# 2_SoC_schdoc.net
KiCad netlist of a schematic drawn in Altium Designer
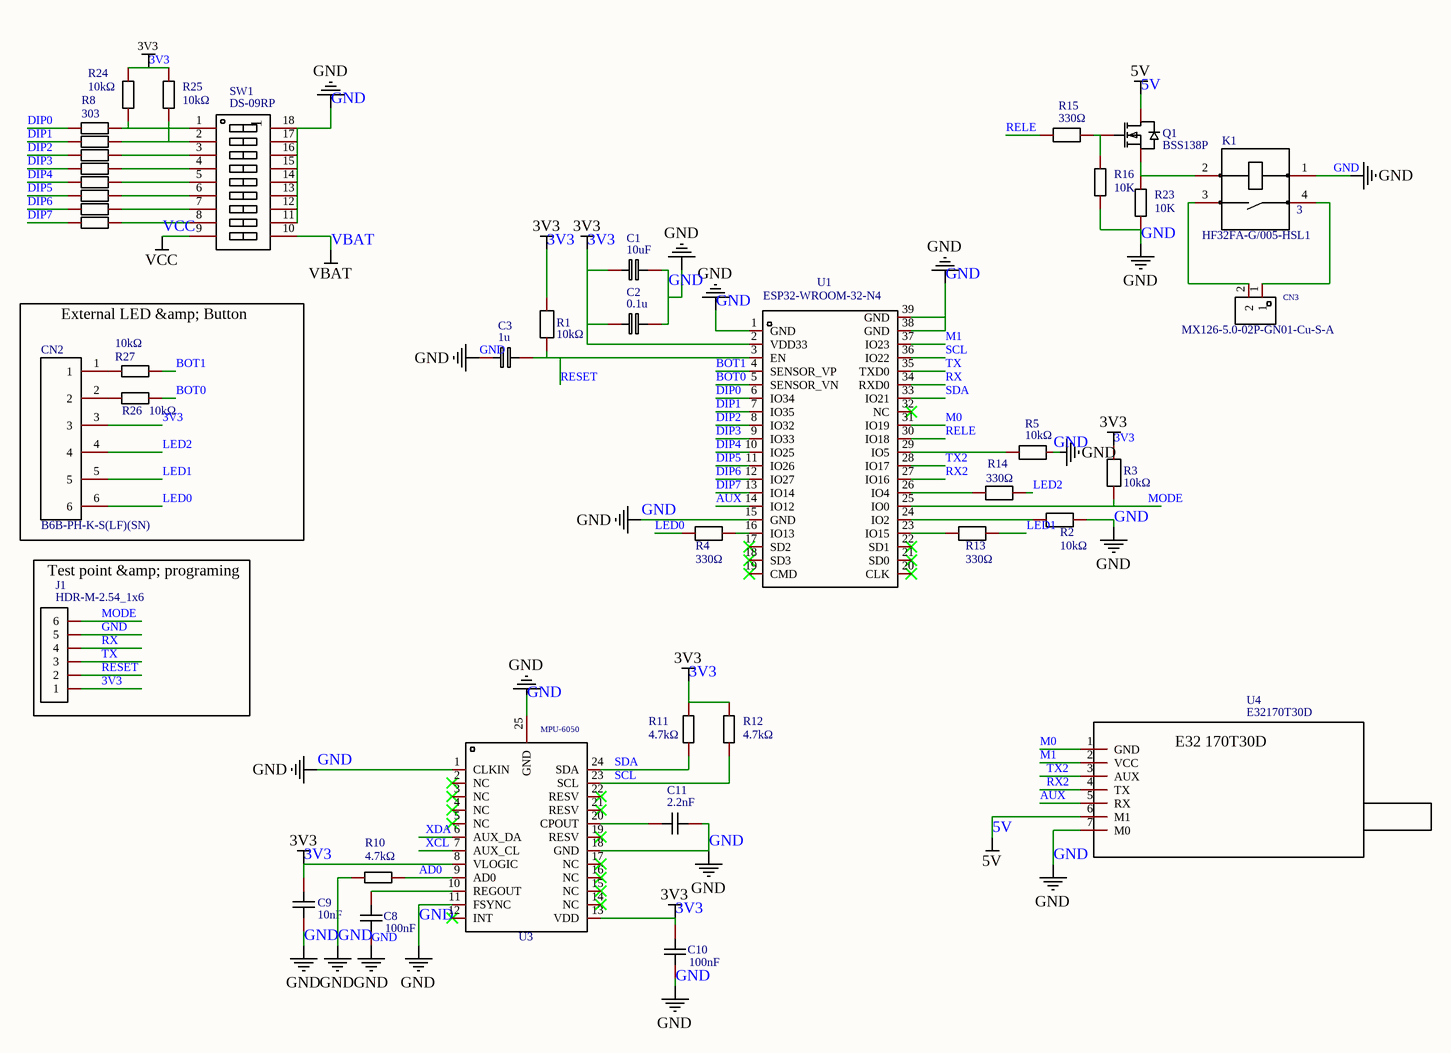
[diagram p0: 2_SoC.schdoc.schdoc]

(export (version "E")
  (design (tool "Eeschema 10.0.6"))
  (components
    (comp (ref "C1")
      (value "10uF")
      (fields
        (field (name "NAME") "10uF")
        (field (name "MANUFACTURER") "SAMSUNG(三星)")
        (field (name "MANUFACTURER PART") "CL10A106MQ8NNNC")
        (field (name "TOLERANCE") "±20%")
      )
      (libsource (lib "altium-import") (part "root_0_CL10A106MQ8NNNC_"))
    )
    (comp (ref "C2")
      (value "0.1u")
      (fields
        (field (name "NAME") "0.1u")
        (field (name "MANUFACTURER PART") "C0603C104K5RACAUTO")
        (field (name "MANUFACTURER") "KEMET(基美)")
      )
      (libsource (lib "altium-import") (part "root_0_0.1u_"))
    )
    (comp (ref "C3")
      (value "1u")
      (fields
        (field (name "NAME") "1u")
        (field (name "MANUFACTURER PART") "CC0603ZRY5V8BB105")
        (field (name "MANUFACTURER") "YAGEO(国巨)")
      )
      (libsource (lib "altium-import") (part "root_0_1u_"))
    )
    (comp (ref "C8")
      (value "100nF")
      (fields
        (field (name "NAME") "100nF")
        (field (name "MANUFACTURER") "FOJAN(富捷)")
        (field (name "MANUFACTURER PART") "FCC0402B104K250AT")
        (field (name "TOLERANCE") "±10%")
      )
      (libsource (lib "altium-import") (part "root_0_FCC0402B104K250AT_"))
    )
    (comp (ref "C9")
      (value "10nF")
      (fields
        (field (name "NAME") "10nF")
        (field (name "MANUFACTURER") "YAGEO(国巨)")
        (field (name "MANUFACTURER PART") "CC0402KRX7R7BB103")
      )
      (libsource (lib "altium-import") (part "root_1_10nF_"))
    )
    (comp (ref "C10")
      (value "100nF")
      (fields
        (field (name "NAME") "100nF")
        (field (name "MANUFACTURER") "FOJAN(富捷)")
        (field (name "MANUFACTURER PART") "FCC0402B104K250AT")
        (field (name "TOLERANCE") "±10%")
      )
      (libsource (lib "altium-import") (part "root_0_FCC0402B104K250AT_"))
    )
    (comp (ref "C11")
      (value "2.2nF")
      (fields
        (field (name "NAME") "2.2nF")
        (field (name "MANUFACTURER") "YAGEO(国巨)")
        (field (name "MANUFACTURER PART") "CC0402KRX7R6BB222")
        (field (name "TOLERANCE") "±10%")
      )
      (libsource (lib "altium-import") (part "root_0_CC0402KRX7R6BB222_"))
    )
    (comp (ref "CN2")
      (value "B6B-PH-K-S(LF)(SN)")
      (fields (field (name "NAME") "B6B-PH-K-S(LF)(SN)") (field (name "MANUFACTURER") "JST"))
      (libsource (lib "altium-import") (part "root_0_B6B-PH-K-S(LF)(SN)_C131342_"))
    )
    (comp (ref "CN3")
      (value "MX126-5.0-02P-GN01-Cu-S-A")
      (fields (field (name "NAME") "MX126-5.0-02P-GN01-Cu-S-A") (field (name "MANUFACTURER") "MAX(迈旭)"))
      (libsource (lib "altium-import") (part "root_3_MX126-5.0-02P-GN01-Cu-S-A_"))
    )
    (comp (ref "J1")
      (value "HDR-M-2.54_1x6")
      (fields (field (name "NAME") "HDR-M-2.54_1x6"))
      (libsource (lib "altium-import") (part "root_2_HDR-M-2.54_1x6_"))
    )
    (comp (ref "K1")
      (value "HF32FA-G/005-HSL1")
      (fields
        (field (name "NAME") "HF32FA-G/005-HSL1")
        (field (name "MANUFACTURER") "HF(宏发)")
        (field (name "NUMBER") "3")
      )
      (libsource (lib "altium-import") (part "root_2_HF32FA-G/005-HSL1_"))
    )
    (comp (ref "Q1")
      (value "BSS138P")
      (fields (field (name "NAME") "BSS138P") (field (name "MANUFACTURER") "ElecSuper(静芯微）"))
      (libsource (lib "altium-import") (part "root_0_BSS138P_"))
    )
    (comp (ref "R1")
      (value "10kΩ")
      (description "Resistance: Tolerance:±1% Tolerance:±1%")
      (fields
        (field (name "NAME") "10kΩ")
        (field (name "MANUFACTURER") "VO(翔胜)")
        (field (name "MANUFACTURER PART") "SCR0402F10K")
      )
      (libsource (lib "altium-import") (part "root_1_SCR0402F10K_"))
    )
    (comp (ref "R2")
      (value "10kΩ")
      (description "Resistance: Tolerance:±1% Tolerance:±1%")
      (fields
        (field (name "NAME") "10kΩ")
        (field (name "MANUFACTURER") "VO(翔胜)")
        (field (name "MANUFACTURER PART") "SCR0402F10K")
      )
      (libsource (lib "altium-import") (part "root_0_SCR0402F10K_"))
    )
    (comp (ref "R3")
      (value "10kΩ")
      (description "Resistance: Tolerance:±1% Tolerance:±1%")
      (fields
        (field (name "NAME") "10kΩ")
        (field (name "MANUFACTURER") "VO(翔胜)")
        (field (name "MANUFACTURER PART") "SCR0402F10K")
      )
      (libsource (lib "altium-import") (part "root_1_SCR0402F10K_"))
    )
    (comp (ref "R4")
      (value "330Ω")
      (description "Resistance: Tolerance:±1% Tolerance:±1%")
      (fields
        (field (name "NAME") "330Ω")
        (field (name "MANUFACTURER") "VO(翔胜)")
        (field (name "MANUFACTURER PART") "SCR0603F330R")
      )
      (libsource (lib "altium-import") (part "root_0_SCR0603F330R_"))
    )
    (comp (ref "R5")
      (value "10kΩ")
      (description "Resistance: Tolerance:±1% Tolerance:±1%")
      (fields
        (field (name "NAME") "10kΩ")
        (field (name "MANUFACTURER") "VO(翔胜)")
        (field (name "MANUFACTURER PART") "SCR0402F10K")
      )
      (libsource (lib "altium-import") (part "root_0_SCR0402F10K_"))
    )
    (comp (ref "R8")
      (value "303")
      (fields (field (name "NAME") "303"))
      (libsource (lib "altium-import") (part "root_0_Res_0603_"))
    )
    (comp (ref "R9") (value "303") (libsource (lib "altium-import") (part "root_0_Res_0603_")))
    (comp (ref "R10")
      (value "4.7kΩ")
      (fields (field (name "NAME") "4.7kΩ"))
      (libsource (lib "altium-import") (part "root_2_Res_0603_"))
    )
    (comp (ref "R11")
      (value "4.7kΩ")
      (fields (field (name "NAME") "4.7kΩ"))
      (libsource (lib "altium-import") (part "root_1_Res_0603_"))
    )
    (comp (ref "R12")
      (value "4.7kΩ")
      (fields (field (name "NAME") "4.7kΩ"))
      (libsource (lib "altium-import") (part "root_1_Res_0603_"))
    )
    (comp (ref "R13")
      (value "330Ω")
      (description "Resistance: Tolerance:±1% Tolerance:±1%")
      (fields
        (field (name "NAME") "330Ω")
        (field (name "MANUFACTURER") "VO(翔胜)")
        (field (name "MANUFACTURER PART") "SCR0603F330R")
      )
      (libsource (lib "altium-import") (part "root_0_SCR0603F330R_"))
    )
    (comp (ref "R14")
      (value "330Ω")
      (description "Resistance: Tolerance:±1% Tolerance:±1%")
      (fields
        (field (name "NAME") "330Ω")
        (field (name "MANUFACTURER") "VO(翔胜)")
        (field (name "MANUFACTURER PART") "SCR0603F330R")
      )
      (libsource (lib "altium-import") (part "root_0_SCR0603F330R_"))
    )
    (comp (ref "R15")
      (value "330Ω")
      (description "Resistance: Tolerance:±1% Tolerance:±1%")
      (fields
        (field (name "NAME") "330Ω")
        (field (name "MANUFACTURER") "VO(翔胜)")
        (field (name "MANUFACTURER PART") "SCR0603F330R")
      )
      (libsource (lib "altium-import") (part "root_0_SCR0603F330R_"))
    )
    (comp (ref "R16")
      (value "10K")
      (fields (field (name "NAME") "10K"))
      (libsource (lib "altium-import") (part "root_1_Res_0603_"))
    )
    (comp (ref "R17") (value "303") (libsource (lib "altium-import") (part "root_0_Res_0603_")))
    (comp (ref "R18") (value "303") (libsource (lib "altium-import") (part "root_0_Res_0603_")))
    (comp (ref "R19") (value "303") (libsource (lib "altium-import") (part "root_0_Res_0603_")))
    (comp (ref "R20") (value "303") (libsource (lib "altium-import") (part "root_0_Res_0603_")))
    (comp (ref "R21") (value "303") (libsource (lib "altium-import") (part "root_0_Res_0603_")))
    (comp (ref "R22") (value "303") (libsource (lib "altium-import") (part "root_0_Res_0603_")))
    (comp (ref "R23")
      (value "10K")
      (fields (field (name "NAME") "10K"))
      (libsource (lib "altium-import") (part "root_1_Res_0603_"))
    )
    (comp (ref "R24")
      (value "10kΩ")
      (description "Resistance: Tolerance:±1% Tolerance:±1%")
      (fields
        (field (name "NAME") "10kΩ")
        (field (name "MANUFACTURER") "VO(翔胜)")
        (field (name "MANUFACTURER PART") "SCR0402F10K")
      )
      (libsource (lib "") (part "root_1_SCR0402F10K__1"))
    )
    (comp (ref "R25")
      (value "10kΩ")
      (description "Resistance: Tolerance:±1% Tolerance:±1%")
      (fields
        (field (name "NAME") "10kΩ")
        (field (name "MANUFACTURER") "VO(翔胜)")
        (field (name "MANUFACTURER PART") "SCR0402F10K")
      )
      (libsource (lib "") (part "root_1_SCR0402F10K__1"))
    )
    (comp (ref "R26")
      (value "10kΩ")
      (description "Resistance: Tolerance:±1% Tolerance:±1%")
      (fields
        (field (name "NAME") "10kΩ")
        (field (name "MANUFACTURER") "VO(翔胜)")
        (field (name "MANUFACTURER PART") "SCR0402F10K")
      )
      (libsource (lib "altium-import") (part "root_2_SCR0402F10K_"))
    )
    (comp (ref "R27")
      (value "10kΩ")
      (description "Resistance: Tolerance:±1% Tolerance:±1%")
      (fields
        (field (name "NAME") "10kΩ")
        (field (name "MANUFACTURER") "VO(翔胜)")
        (field (name "MANUFACTURER PART") "SCR0402F10K")
      )
      (libsource (lib "altium-import") (part "root_2_SCR0402F10K_"))
    )
    (comp (ref "SW1")
      (value "DS-09RP")
      (fields (field (name "NAME") "DS-09RP") (field (name "MANUFACTURER") "韩国韩荣"))
      (libsource (lib "altium-import") (part "root_0_DS-09RP_C458083_"))
    )
    (comp (ref "U1")
      (value "ESP32-WROOM-32-N4")
      (fields (field (name "NAME") "ESP32-WROOM-32-N4") (field (name "MANUFACTURER") "ESPRESSIF(乐鑫)"))
      (libsource (lib "altium-import") (part "root_0_ESP32-WROOM-32-N4_"))
    )
    (comp (ref "U3")
      (value "MPU-6050")
      (fields (field (name "DEVICE") "MPU-6050") (field (name "MANUFACTURER") "TDK InvenSense(应美盛)"))
      (libsource (lib "altium-import") (part "root_0_MPU-6050_"))
    )
    (comp (ref "U4")
      (value "E32170T30D")
      (fields (field (name "NAME") "E32170T30D"))
      (libsource (lib "altium-import") (part "root_0_E32170T30D_"))
    )
  )
  (nets
    (net (code "1") (name "/AD0") (class "Default")
      (node (ref "R10") (pin "1") (pinfunction "1_1") (pintype "passive"))
      (node (ref "U3") (pin "9") (pinfunction "AD0_9") (pintype "passive"))
    )
    (net (code "2") (name "/AUX") (class "Default")
      (node (ref "U1") (pin "14") (pinfunction "IO12_14") (pintype "passive"))
      (node (ref "U4") (pin "5") (pinfunction "RX_5") (pintype "passive"))
    )
    (net (code "3") (name "/BOT0") (class "Default")
      (node (ref "R26") (pin "1") (pinfunction "1_1") (pintype "passive"))
      (node (ref "U1") (pin "5") (pinfunction "SENSOR_VN_5") (pintype "passive"))
    )
    (net (code "4") (name "/BOT1") (class "Default")
      (node (ref "R27") (pin "1") (pinfunction "1_1") (pintype "passive"))
      (node (ref "U1") (pin "4") (pinfunction "SENSOR_VP_4") (pintype "passive"))
    )
    (net (code "5") (name "/DIP0") (class "Default")
      (node (ref "R8") (pin "1") (pinfunction "1_1") (pintype "passive"))
      (node (ref "U1") (pin "6") (pinfunction "IO34_6") (pintype "passive"))
    )
    (net (code "6") (name "/DIP1") (class "Default")
      (node (ref "R9") (pin "1") (pinfunction "1_1") (pintype "passive"))
      (node (ref "U1") (pin "7") (pinfunction "IO35_7") (pintype "passive"))
    )
    (net (code "7") (name "/DIP2") (class "Default")
      (node (ref "R17") (pin "1") (pinfunction "1_1") (pintype "passive"))
      (node (ref "U1") (pin "8") (pinfunction "IO32_8") (pintype "passive"))
    )
    (net (code "8") (name "/DIP3") (class "Default")
      (node (ref "R18") (pin "1") (pinfunction "1_1") (pintype "passive"))
      (node (ref "U1") (pin "9") (pinfunction "IO33_9") (pintype "passive"))
    )
    (net (code "9") (name "/DIP4") (class "Default")
      (node (ref "R19") (pin "1") (pinfunction "1_1") (pintype "passive"))
      (node (ref "U1") (pin "10") (pinfunction "IO25_10") (pintype "passive"))
    )
    (net (code "10") (name "/DIP5") (class "Default")
      (node (ref "R20") (pin "1") (pinfunction "1_1") (pintype "passive"))
      (node (ref "U1") (pin "11") (pinfunction "IO26_11") (pintype "passive"))
    )
    (net (code "11") (name "/DIP6") (class "Default")
      (node (ref "R21") (pin "1") (pinfunction "1_1") (pintype "passive"))
      (node (ref "U1") (pin "12") (pinfunction "IO27_12") (pintype "passive"))
    )
    (net (code "12") (name "/DIP7") (class "Default")
      (node (ref "R22") (pin "1") (pinfunction "1_1") (pintype "passive"))
      (node (ref "U1") (pin "13") (pinfunction "IO14_13") (pintype "passive"))
    )
    (net (code "13") (name "/LED0") (class "Default")
      (node (ref "CN2") (pin "6") (pinfunction "6_6") (pintype "passive"))
      (node (ref "R4") (pin "1") (pinfunction "1_1") (pintype "passive"))
    )
    (net (code "14") (name "/LED1") (class "Default")
      (node (ref "CN2") (pin "5") (pinfunction "5_5") (pintype "passive"))
      (node (ref "R13") (pin "2") (pinfunction "2_2") (pintype "passive"))
    )
    (net (code "15") (name "/LED2") (class "Default")
      (node (ref "CN2") (pin "4") (pinfunction "4_4") (pintype "passive"))
      (node (ref "R14") (pin "2") (pinfunction "2_2") (pintype "passive"))
    )
    (net (code "16") (name "/M0") (class "Default")
      (node (ref "U1") (pin "31") (pinfunction "IO19_31") (pintype "passive"))
      (node (ref "U4") (pin "1") (pinfunction "GND_1") (pintype "passive"))
    )
    (net (code "17") (name "/M1") (class "Default")
      (node (ref "U1") (pin "37") (pinfunction "IO23_37") (pintype "passive"))
      (node (ref "U4") (pin "2") (pinfunction "VCC_2") (pintype "passive"))
    )
    (net (code "18") (name "/MODE") (class "Default")
      (node (ref "J1") (pin "6") (pinfunction "6_6") (pintype "passive"))
      (node (ref "R3") (pin "1") (pinfunction "1_1") (pintype "passive"))
      (node (ref "U1") (pin "25") (pinfunction "IO0_25") (pintype "passive"))
    )
    (net (code "19") (name "/RELE") (class "Default")
      (node (ref "R15") (pin "1") (pinfunction "1_1") (pintype "passive"))
      (node (ref "U1") (pin "30") (pinfunction "IO18_30") (pintype "passive"))
    )
    (net (code "20") (name "/RESET") (class "Default")
      (node (ref "C3") (pin "2") (pinfunction "2_2") (pintype "passive"))
      (node (ref "J1") (pin "2") (pinfunction "2_2") (pintype "passive"))
      (node (ref "R1") (pin "1") (pinfunction "1_1") (pintype "passive"))
      (node (ref "U1") (pin "3") (pinfunction "EN_3") (pintype "passive"))
    )
    (net (code "21") (name "/RX") (class "Default")
      (node (ref "J1") (pin "4") (pinfunction "4_4") (pintype "passive"))
      (node (ref "U1") (pin "34") (pinfunction "RXD0_34") (pintype "passive"))
    )
    (net (code "22") (name "/RX2") (class "Default")
      (node (ref "U1") (pin "27") (pinfunction "IO16_27") (pintype "passive"))
      (node (ref "U4") (pin "4") (pinfunction "TX_4") (pintype "passive"))
    )
    (net (code "23") (name "/SCL") (class "Default")
      (node (ref "R12") (pin "1") (pinfunction "1_1") (pintype "passive"))
      (node (ref "U1") (pin "36") (pinfunction "IO22_36") (pintype "passive"))
      (node (ref "U3") (pin "23") (pinfunction "SCL_23") (pintype "passive"))
    )
    (net (code "24") (name "/SDA") (class "Default")
      (node (ref "R11") (pin "1") (pinfunction "1_1") (pintype "passive"))
      (node (ref "U1") (pin "33") (pinfunction "IO21_33") (pintype "passive"))
      (node (ref "U3") (pin "24") (pinfunction "SDA_24") (pintype "passive"))
    )
    (net (code "25") (name "/TX") (class "Default")
      (node (ref "J1") (pin "3") (pinfunction "3_3") (pintype "passive"))
      (node (ref "U1") (pin "35") (pinfunction "TXD0_35") (pintype "passive"))
    )
    (net (code "26") (name "/TX2") (class "Default")
      (node (ref "U1") (pin "28") (pinfunction "IO17_28") (pintype "passive"))
      (node (ref "U4") (pin "3") (pinfunction "AUX_3") (pintype "passive"))
    )
    (net (code "27") (name "/XCL") (class "Default")
      (node (ref "U3") (pin "7") (pinfunction "AUX_CL_7") (pintype "passive"))
    )
    (net (code "28") (name "/XDA") (class "Default")
      (node (ref "U3") (pin "6") (pinfunction "AUX_DA_6") (pintype "passive"))
    )
    (net (code "29") (name "3V3") (class "Default")
      (node (ref "C1") (pin "1") (pinfunction "1_1") (pintype "passive"))
      (node (ref "C10") (pin "2") (pinfunction "2_2") (pintype "passive"))
      (node (ref "C2") (pin "1") (pinfunction "1_1") (pintype "passive"))
      (node (ref "C9") (pin "1") (pinfunction "1_1") (pintype "passive"))
      (node (ref "CN2") (pin "3") (pinfunction "3_3") (pintype "passive"))
      (node (ref "J1") (pin "1") (pinfunction "1_1") (pintype "passive"))
      (node (ref "R1") (pin "2") (pinfunction "2_2") (pintype "passive"))
      (node (ref "R11") (pin "2") (pinfunction "2_2") (pintype "passive"))
      (node (ref "R12") (pin "2") (pinfunction "2_2") (pintype "passive"))
      (node (ref "R24") (pin "2") (pinfunction "2_2") (pintype "passive"))
      (node (ref "R25") (pin "2") (pinfunction "2_2") (pintype "passive"))
      (node (ref "R3") (pin "2") (pinfunction "2_2") (pintype "passive"))
      (node (ref "U1") (pin "2") (pinfunction "VDD33_2") (pintype "passive"))
      (node (ref "U3") (pin "13") (pinfunction "VDD_13") (pintype "passive"))
      (node (ref "U3") (pin "8") (pinfunction "VLOGIC_8") (pintype "passive"))
    )
    (net (code "30") (name "5V") (class "Default")
      (node (ref "Q1") (pin "3") (pinfunction "D_3") (pintype "passive"))
      (node (ref "U4") (pin "6") (pinfunction "M1_6") (pintype "passive"))
    )
    (net (code "31") (name "GND") (class "Default")
      (node (ref "C1") (pin "2") (pinfunction "2_2") (pintype "passive"))
      (node (ref "C10") (pin "1") (pinfunction "1_1") (pintype "passive"))
      (node (ref "C11") (pin "2") (pinfunction "2_2") (pintype "passive"))
      (node (ref "C2") (pin "2") (pinfunction "2_2") (pintype "passive"))
      (node (ref "C3") (pin "1") (pinfunction "1_1") (pintype "passive"))
      (node (ref "C8") (pin "1") (pinfunction "1_1") (pintype "passive"))
      (node (ref "C9") (pin "2") (pinfunction "2_2") (pintype "passive"))
      (node (ref "J1") (pin "5") (pinfunction "5_5") (pintype "passive"))
      (node (ref "K1") (pin "1") (pinfunction "1_1") (pintype "passive"))
      (node (ref "R10") (pin "2") (pinfunction "2_2") (pintype "passive"))
      (node (ref "R16") (pin "1") (pinfunction "1_1") (pintype "passive"))
      (node (ref "R2") (pin "2") (pinfunction "2_2") (pintype "passive"))
      (node (ref "R23") (pin "1") (pinfunction "1_1") (pintype "passive"))
      (node (ref "R5") (pin "2") (pinfunction "2_2") (pintype "passive"))
      (node (ref "SW1") (pin "11") (pinfunction "PIN11_11") (pintype "passive"))
      (node (ref "SW1") (pin "12") (pinfunction "PIN12_12") (pintype "passive"))
      (node (ref "SW1") (pin "13") (pinfunction "PIN13_13") (pintype "passive"))
      (node (ref "SW1") (pin "14") (pinfunction "PIN14_14") (pintype "passive"))
      (node (ref "SW1") (pin "15") (pinfunction "PIN15_15") (pintype "passive"))
      (node (ref "SW1") (pin "16") (pinfunction "PIN16_16") (pintype "passive"))
      (node (ref "SW1") (pin "17") (pinfunction "PIN17_17") (pintype "passive"))
      (node (ref "SW1") (pin "18") (pinfunction "PIN18_18") (pintype "passive"))
      (node (ref "U1") (pin "1") (pinfunction "GND_1") (pintype "passive"))
      (node (ref "U1") (pin "15") (pinfunction "GND_15") (pintype "passive"))
      (node (ref "U1") (pin "38") (pinfunction "GND_38") (pintype "passive"))
      (node (ref "U1") (pin "39") (pinfunction "GND_39") (pintype "passive"))
      (node (ref "U3") (pin "1") (pinfunction "CLKIN_1") (pintype "passive"))
      (node (ref "U3") (pin "11") (pinfunction "FSYNC_11") (pintype "passive"))
      (node (ref "U3") (pin "18") (pinfunction "GND_18") (pintype "passive"))
      (node (ref "U3") (pin "25") (pinfunction "GND_25") (pintype "passive"))
      (node (ref "U4") (pin "7") (pinfunction "M0_7") (pintype "passive"))
    )
    (net (code "32") (name "Net-(CN2-Pad1)") (class "Default")
      (node (ref "CN2") (pin "1") (pinfunction "1_1") (pintype "passive"))
      (node (ref "R27") (pin "2") (pinfunction "2_2") (pintype "passive"))
    )
    (net (code "33") (name "Net-(CN2-Pad2)") (class "Default")
      (node (ref "CN2") (pin "2") (pinfunction "2_2") (pintype "passive"))
      (node (ref "R26") (pin "2") (pinfunction "2_2") (pintype "passive"))
    )
    (net (code "34") (name "Net-(CN3-Pad1)") (class "Default")
      (node (ref "CN3") (pin "1") (pinfunction "1_1") (pintype "passive"))
      (node (ref "K1") (pin "4") (pinfunction "4_4") (pintype "passive"))
    )
    (net (code "35") (name "Net-(CN3-Pad2)") (class "Default")
      (node (ref "CN3") (pin "2") (pinfunction "2_2") (pintype "passive"))
      (node (ref "K1") (pin "3") (pinfunction "3_3") (pintype "passive"))
    )
    (net (code "36") (name "Net-(Q1-G)") (class "Default")
      (node (ref "Q1") (pin "1") (pinfunction "G_1") (pintype "passive"))
      (node (ref "R15") (pin "2") (pinfunction "2_2") (pintype "passive"))
      (node (ref "R16") (pin "2") (pinfunction "2_2") (pintype "passive"))
    )
    (net (code "37") (name "Net-(Q1-S)") (class "Default")
      (node (ref "K1") (pin "2") (pinfunction "2_2") (pintype "passive"))
      (node (ref "Q1") (pin "2") (pinfunction "S_2") (pintype "passive"))
      (node (ref "R23") (pin "2") (pinfunction "2_2") (pintype "passive"))
    )
    (net (code "38") (name "Net-(SW1-PIN1)") (class "Default")
      (node (ref "R24") (pin "1") (pinfunction "1_1") (pintype "passive"))
      (node (ref "R8") (pin "2") (pinfunction "2_2") (pintype "passive"))
      (node (ref "SW1") (pin "1") (pinfunction "PIN1_1") (pintype "passive"))
    )
    (net (code "39") (name "Net-(SW1-PIN2)") (class "Default")
      (node (ref "R25") (pin "1") (pinfunction "1_1") (pintype "passive"))
      (node (ref "R9") (pin "2") (pinfunction "2_2") (pintype "passive"))
      (node (ref "SW1") (pin "2") (pinfunction "PIN2_2") (pintype "passive"))
    )
    (net (code "40") (name "Net-(SW1-PIN3)") (class "Default")
      (node (ref "R17") (pin "2") (pinfunction "2_2") (pintype "passive"))
      (node (ref "SW1") (pin "3") (pinfunction "PIN3_3") (pintype "passive"))
    )
    (net (code "41") (name "Net-(SW1-PIN4)") (class "Default")
      (node (ref "R18") (pin "2") (pinfunction "2_2") (pintype "passive"))
      (node (ref "SW1") (pin "4") (pinfunction "PIN4_4") (pintype "passive"))
    )
    (net (code "42") (name "Net-(SW1-PIN5)") (class "Default")
      (node (ref "R19") (pin "2") (pinfunction "2_2") (pintype "passive"))
      (node (ref "SW1") (pin "5") (pinfunction "PIN5_5") (pintype "passive"))
    )
    (net (code "43") (name "Net-(SW1-PIN6)") (class "Default")
      (node (ref "R20") (pin "2") (pinfunction "2_2") (pintype "passive"))
      (node (ref "SW1") (pin "6") (pinfunction "PIN6_6") (pintype "passive"))
    )
    (net (code "44") (name "Net-(SW1-PIN7)") (class "Default")
      (node (ref "R21") (pin "2") (pinfunction "2_2") (pintype "passive"))
      (node (ref "SW1") (pin "7") (pinfunction "PIN7_7") (pintype "passive"))
    )
    (net (code "45") (name "Net-(SW1-PIN8)") (class "Default")
      (node (ref "R22") (pin "2") (pinfunction "2_2") (pintype "passive"))
      (node (ref "SW1") (pin "8") (pinfunction "PIN8_8") (pintype "passive"))
    )
    (net (code "46") (name "Net-(U1-IO2)") (class "Default")
      (node (ref "R2") (pin "1") (pinfunction "1_1") (pintype "passive"))
      (node (ref "U1") (pin "24") (pinfunction "IO2_24") (pintype "passive"))
    )
    (net (code "47") (name "Net-(U1-IO4)") (class "Default")
      (node (ref "R14") (pin "1") (pinfunction "1_1") (pintype "passive"))
      (node (ref "U1") (pin "26") (pinfunction "IO4_26") (pintype "passive"))
    )
    (net (code "48") (name "Net-(U1-IO5)") (class "Default")
      (node (ref "R5") (pin "1") (pinfunction "1_1") (pintype "passive"))
      (node (ref "U1") (pin "29") (pinfunction "IO5_29") (pintype "passive"))
    )
    (net (code "49") (name "Net-(U1-IO13)") (class "Default")
      (node (ref "R4") (pin "2") (pinfunction "2_2") (pintype "passive"))
      (node (ref "U1") (pin "16") (pinfunction "IO13_16") (pintype "passive"))
    )
    (net (code "50") (name "Net-(U1-IO15)") (class "Default")
      (node (ref "R13") (pin "1") (pinfunction "1_1") (pintype "passive"))
      (node (ref "U1") (pin "23") (pinfunction "IO15_23") (pintype "passive"))
    )
    (net (code "51") (name "Net-(U3-CPOUT)") (class "Default")
      (node (ref "C11") (pin "1") (pinfunction "1_1") (pintype "passive"))
      (node (ref "U3") (pin "20") (pinfunction "CPOUT_20") (pintype "passive"))
    )
    (net (code "52") (name "Net-(U3-REGOUT)") (class "Default")
      (node (ref "C8") (pin "2") (pinfunction "2_2") (pintype "passive"))
      (node (ref "U3") (pin "10") (pinfunction "REGOUT_10") (pintype "passive"))
    )
    (net (code "53") (name "VBAT") (class "Default")
      (node (ref "SW1") (pin "10") (pinfunction "PIN10_10") (pintype "passive"))
    )
    (net (code "54") (name "VCC") (class "Default")
      (node (ref "SW1") (pin "9") (pinfunction "PIN9_9") (pintype "passive"))
    )
    (net (code "55") (name "unconnected-(U1-CLK-Pad20)") (class "Default")
      (node (ref "U1") (pin "20") (pinfunction "CLK_20") (pintype "passive+no_connect"))
    )
    (net (code "56") (name "unconnected-(U1-CMD-Pad19)") (class "Default")
      (node (ref "U1") (pin "19") (pinfunction "CMD_19") (pintype "passive+no_connect"))
    )
    (net (code "57") (name "unconnected-(U1-NC-Pad32)") (class "Default")
      (node (ref "U1") (pin "32") (pinfunction "NC_32") (pintype "passive+no_connect"))
    )
    (net (code "58") (name "unconnected-(U1-SD0-Pad21)") (class "Default")
      (node (ref "U1") (pin "21") (pinfunction "SD0_21") (pintype "passive+no_connect"))
    )
    (net (code "59") (name "unconnected-(U1-SD1-Pad22)") (class "Default")
      (node (ref "U1") (pin "22") (pinfunction "SD1_22") (pintype "passive+no_connect"))
    )
    (net (code "60") (name "unconnected-(U1-SD2-Pad17)") (class "Default")
      (node (ref "U1") (pin "17") (pinfunction "SD2_17") (pintype "passive+no_connect"))
    )
    (net (code "61") (name "unconnected-(U1-SD3-Pad18)") (class "Default")
      (node (ref "U1") (pin "18") (pinfunction "SD3_18") (pintype "passive+no_connect"))
    )
    (net (code "62") (name "unconnected-(U3-INT-Pad12)") (class "Default")
      (node (ref "U3") (pin "12") (pinfunction "INT_12") (pintype "passive+no_connect"))
    )
    (net (code "63") (name "unconnected-(U3-NC-Pad2)") (class "Default")
      (node (ref "U3") (pin "2") (pinfunction "NC_2") (pintype "passive+no_connect"))
    )
    (net (code "64") (name "unconnected-(U3-NC-Pad3)") (class "Default")
      (node (ref "U3") (pin "3") (pinfunction "NC_3") (pintype "passive+no_connect"))
    )
    (net (code "65") (name "unconnected-(U3-NC-Pad4)") (class "Default")
      (node (ref "U3") (pin "4") (pinfunction "NC_4") (pintype "passive+no_connect"))
    )
    (net (code "66") (name "unconnected-(U3-NC-Pad5)") (class "Default")
      (node (ref "U3") (pin "5") (pinfunction "NC_5") (pintype "passive+no_connect"))
    )
    (net (code "67") (name "unconnected-(U3-NC-Pad14)") (class "Default")
      (node (ref "U3") (pin "14") (pinfunction "NC_14") (pintype "passive+no_connect"))
    )
    (net (code "68") (name "unconnected-(U3-NC-Pad15)") (class "Default")
      (node (ref "U3") (pin "15") (pinfunction "NC_15") (pintype "passive+no_connect"))
    )
    (net (code "69") (name "unconnected-(U3-NC-Pad16)") (class "Default")
      (node (ref "U3") (pin "16") (pinfunction "NC_16") (pintype "passive+no_connect"))
    )
    (net (code "70") (name "unconnected-(U3-NC-Pad17)") (class "Default")
      (node (ref "U3") (pin "17") (pinfunction "NC_17") (pintype "passive+no_connect"))
    )
    (net (code "71") (name "unconnected-(U3-RESV-Pad19)") (class "Default")
      (node (ref "U3") (pin "19") (pinfunction "RESV_19") (pintype "passive+no_connect"))
    )
    (net (code "72") (name "unconnected-(U3-RESV-Pad21)") (class "Default")
      (node (ref "U3") (pin "21") (pinfunction "RESV_21") (pintype "passive+no_connect"))
    )
    (net (code "73") (name "unconnected-(U3-RESV-Pad22)") (class "Default")
      (node (ref "U3") (pin "22") (pinfunction "RESV_22") (pintype "passive+no_connect"))
    )
  )
)
